# Amp_Speaker.net
KiCad netlist of a schematic drawn in EAGLE
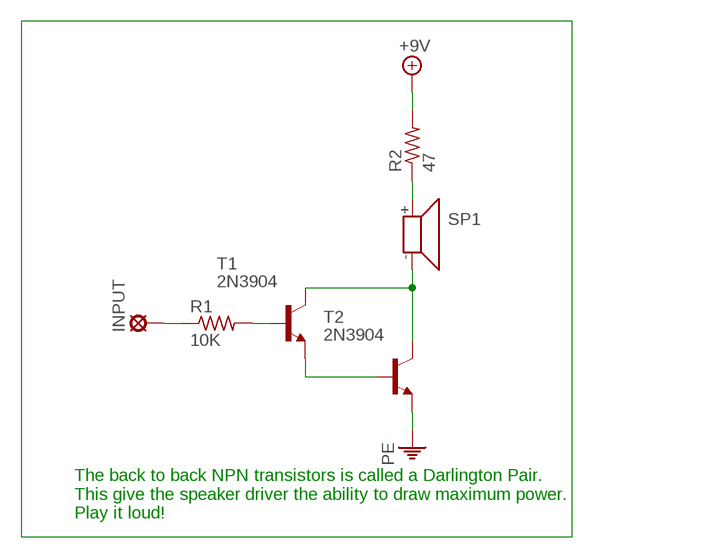
[diagram p0: schematic, sheet 1]

(export (version "E")
  (design (tool "Eeschema 10.0.6"))
  (components
    (comp (ref "INPUT")
      (value "MCS10B")
      (footprint "eagle-import:MCS10B")
      (libsource (lib "eagle-import") (part "MCS10B"))
    )
    (comp (ref "R1")
      (value "10K")
      (footprint "eagle-import:0204_7")
      (libsource (lib "eagle-import") (part "R-US_0204/7"))
    )
    (comp (ref "R2")
      (value "47")
      (footprint "eagle-import:0204_7")
      (libsource (lib "eagle-import") (part "R-US_0204/7"))
    )
    (comp (ref "SP1")
      (value "SMS-1308MS-2-R")
      (footprint "eagle-import:SMS-1308MS-2-R")
      (libsource (lib "eagle-import") (part "SMS-1308MS-2-R"))
    )
    (comp (ref "T1")
      (value "2N3904")
      (footprint "eagle-import:TO92")
      (libsource (lib "eagle-import") (part "2N3904"))
    )
    (comp (ref "T2")
      (value "2N3904")
      (footprint "eagle-import:TO92")
      (libsource (lib "eagle-import") (part "2N3904"))
    )
  )
  (nets
    (net (code "1") (name "+9V") (class "Default")
      (node (ref "R2") (pin "2") (pinfunction "2_2") (pintype "passive"))
    )
    (net (code "2") (name "Net-(INPUT-PadMP)") (class "Default")
      (node (ref "INPUT") (pin "MP") (pinfunction "MP_MP") (pintype "passive"))
      (node (ref "R1") (pin "1") (pinfunction "1_1") (pintype "passive"))
    )
    (net (code "3") (name "Net-(SP1-1)") (class "Default")
      (node (ref "R2") (pin "1") (pinfunction "1_1") (pintype "passive"))
      (node (ref "SP1") (pin "+") (pinfunction "1_+") (pintype "passive"))
    )
    (net (code "4") (name "Net-(SP1-2)") (class "Default")
      (node (ref "SP1") (pin "-") (pinfunction "2_-") (pintype "passive"))
      (node (ref "T1") (pin "1") (pinfunction "C_1") (pintype "passive"))
      (node (ref "T2") (pin "1") (pinfunction "C_1") (pintype "passive"))
    )
    (net (code "5") (name "Net-(T1-B)") (class "Default")
      (node (ref "R1") (pin "2") (pinfunction "2_2") (pintype "passive"))
      (node (ref "T1") (pin "2") (pinfunction "B_2") (pintype "passive"))
    )
    (net (code "6") (name "Net-(T1-E)") (class "Default")
      (node (ref "T1") (pin "3") (pinfunction "E_3") (pintype "passive"))
      (node (ref "T2") (pin "2") (pinfunction "B_2") (pintype "passive"))
    )
    (net (code "7") (name "PE") (class "Default")
      (node (ref "T2") (pin "3") (pinfunction "E_3") (pintype "passive"))
    )
  )
)
